# sch.net
KiCad netlist of a schematic drawn in Altium Designer
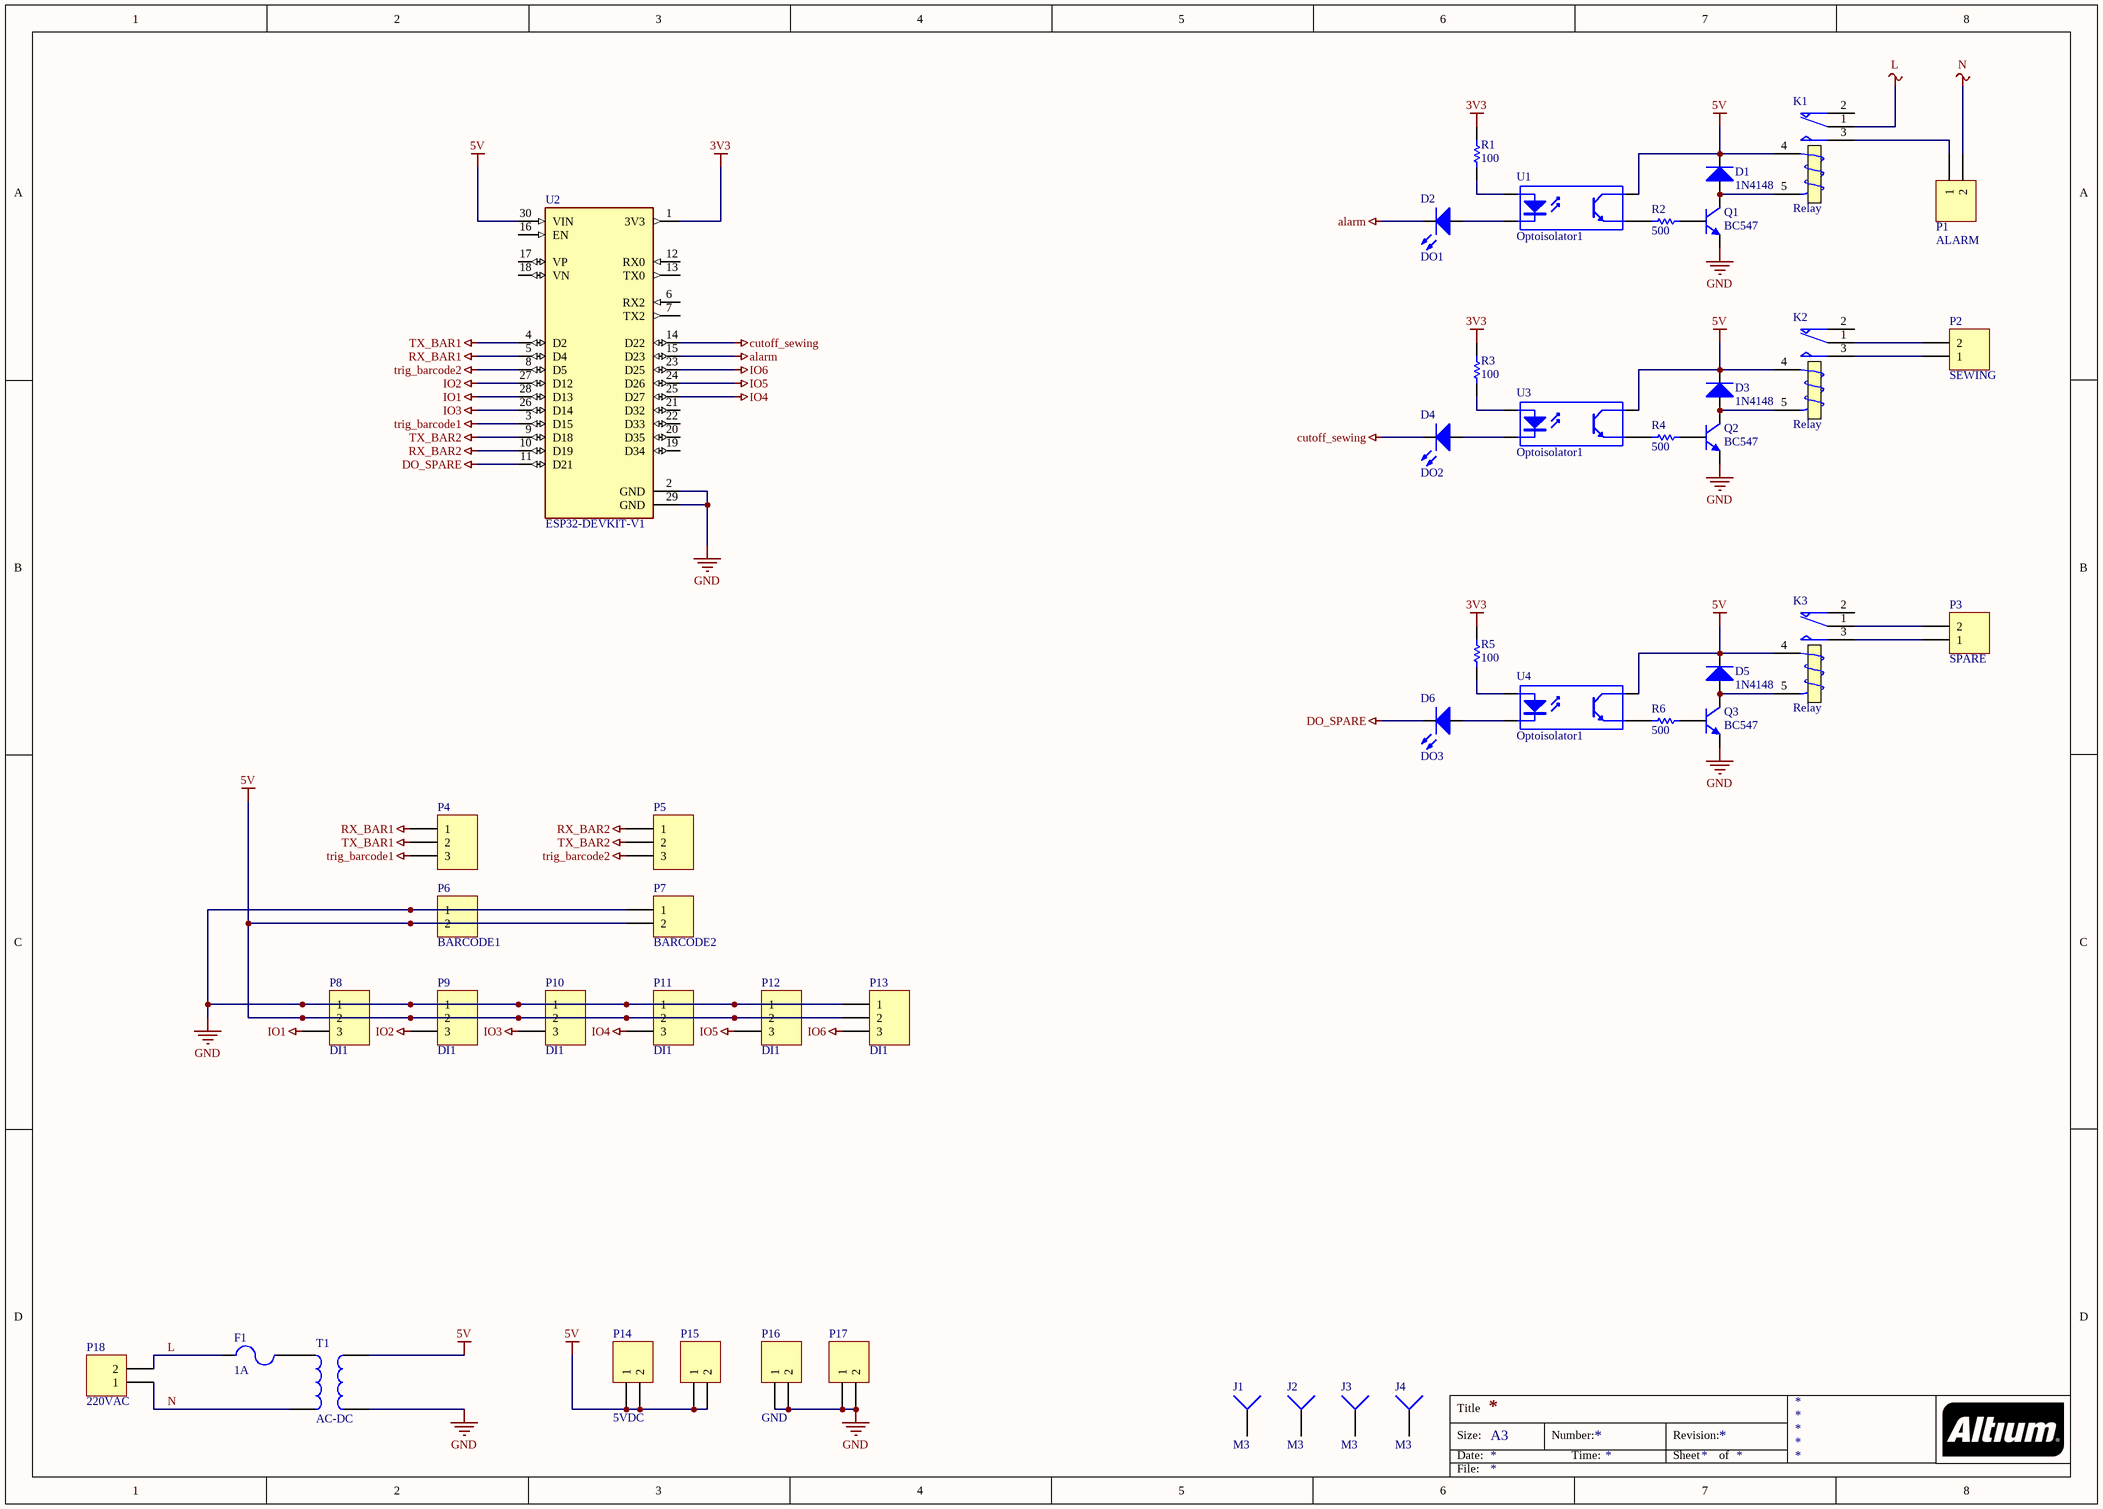
[diagram p0: sch.SchDoc]

(export (version "E")
  (design (tool "Eeschema 10.0.6"))
  (components
    (comp (ref "D1")
      (value "1N4148")
      (footprint "weerachai:D4148")
      (description "Default Diode")
      (fields (field (name "PUBLISHER") "Altium Limited"))
      (libsource (lib "weerachai") (part "Diode"))
    )
    (comp (ref "D2")
      (value "DO1")
      (footprint "weerachai:LED")
      (description "Typical INFRARED GaAs LED")
      (fields (field (name "PUBLISHER") "Altium Limited"))
      (libsource (lib "weerachai") (part "LED0"))
    )
    (comp (ref "D3")
      (value "1N4148")
      (footprint "weerachai:D4148")
      (description "Default Diode")
      (fields (field (name "PUBLISHER") "Altium Limited"))
      (libsource (lib "weerachai") (part "Diode"))
    )
    (comp (ref "D4")
      (value "DO2")
      (footprint "weerachai:LED")
      (description "Typical INFRARED GaAs LED")
      (fields (field (name "PUBLISHER") "Altium Limited"))
      (libsource (lib "weerachai") (part "LED0"))
    )
    (comp (ref "D5")
      (value "1N4148")
      (footprint "weerachai:D4148")
      (description "Default Diode")
      (fields (field (name "PUBLISHER") "Altium Limited"))
      (libsource (lib "weerachai") (part "Diode"))
    )
    (comp (ref "D6")
      (value "DO3")
      (footprint "weerachai:LED")
      (description "Typical INFRARED GaAs LED")
      (fields (field (name "PUBLISHER") "Altium Limited"))
      (libsource (lib "weerachai") (part "LED0"))
    )
    (comp (ref "F1")
      (value "1A")
      (footprint "weerachai:CAP5W")
      (description "Fuse")
      (fields (field (name "PUBLISHER") "Altium Limited"))
      (libsource (lib "weerachai") (part "Fuse 2"))
    )
    (comp (ref "J1")
      (value "M3")
      (footprint "weerachai:PAD")
      (description "Socket")
      (fields (field (name "PUBLISHER") "Altium Limited"))
      (libsource (lib "weerachai") (part "Socket"))
    )
    (comp (ref "J2")
      (value "M3")
      (footprint "weerachai:PAD")
      (description "Socket")
      (fields (field (name "PUBLISHER") "Altium Limited"))
      (libsource (lib "weerachai") (part "Socket"))
    )
    (comp (ref "J3")
      (value "M3")
      (footprint "weerachai:PAD")
      (description "Socket")
      (fields (field (name "PUBLISHER") "Altium Limited"))
      (libsource (lib "weerachai") (part "Socket"))
    )
    (comp (ref "J4")
      (value "M3")
      (footprint "weerachai:PAD")
      (description "Socket")
      (fields (field (name "PUBLISHER") "Altium Limited"))
      (libsource (lib "weerachai") (part "Socket"))
    )
    (comp (ref "K1")
      (value "Relay")
      (footprint "weerachai:RELAY1CON_REV")
      (description "SPDT Relay")
      (fields (field (name "PUBLISHER") "Altium Limited"))
      (libsource (lib "weerachai") (part "Relay"))
    )
    (comp (ref "K2")
      (value "Relay")
      (footprint "weerachai:RELAY1CON_REV")
      (description "SPDT Relay")
      (fields (field (name "PUBLISHER") "Altium Limited"))
      (libsource (lib "weerachai") (part "Relay"))
    )
    (comp (ref "K3")
      (value "Relay")
      (footprint "weerachai:RELAY1CON_REV")
      (description "SPDT Relay")
      (fields (field (name "PUBLISHER") "Altium Limited"))
      (libsource (lib "weerachai") (part "Relay"))
    )
    (comp (ref "P1")
      (value "ALARM")
      (footprint "weerachai:KF142V-5.08-P2")
      (description "Header, 2-Pin")
      (fields (field (name "PUBLISHER") "Altium Limited"))
      (libsource (lib "") (part "Header 2_1"))
    )
    (comp (ref "P2")
      (value "SEWING")
      (footprint "weerachai:KF142V-5.08-P2")
      (description "Header, 2-Pin")
      (fields (field (name "PUBLISHER") "Altium Limited"))
      (libsource (lib "Miscellaneous Connectors") (part "Header 2"))
    )
    (comp (ref "P3")
      (value "SPARE")
      (footprint "weerachai:KF142V-5.08-P2")
      (description "Header, 2-Pin")
      (fields (field (name "PUBLISHER") "Altium Limited"))
      (libsource (lib "Miscellaneous Connectors") (part "Header 2"))
    )
    (comp (ref "P4")
      (value "~")
      (footprint "weerachai:CONNECT_2.54_(3)")
      (description "Header, 3-Pin")
      (fields (field (name "PUBLISHER") "Altium Limited"))
      (libsource (lib "Miscellaneous Connectors") (part "Header 3"))
    )
    (comp (ref "P5")
      (value "~")
      (footprint "weerachai:CONNECT_2.54_(3)")
      (description "Header, 3-Pin")
      (fields (field (name "PUBLISHER") "Altium Limited"))
      (libsource (lib "Miscellaneous Connectors") (part "Header 3"))
    )
    (comp (ref "P6")
      (value "BARCODE1")
      (footprint "weerachai:CONNECT_2.54_(2)")
      (description "Header, 2-Pin")
      (fields (field (name "PUBLISHER") "Altium Limited"))
      (libsource (lib "") (part "Header 2_2"))
    )
    (comp (ref "P7")
      (value "BARCODE2")
      (footprint "weerachai:CONNECT_2.54_(2)")
      (description "Header, 2-Pin")
      (fields (field (name "PUBLISHER") "Altium Limited"))
      (libsource (lib "") (part "Header 2_2"))
    )
    (comp (ref "P8")
      (value "DI1")
      (footprint "weerachai:CONNECT_2.54_(3)")
      (description "Header, 3-Pin")
      (fields (field (name "PUBLISHER") "Altium Limited"))
      (libsource (lib "Miscellaneous Connectors") (part "Header 3"))
    )
    (comp (ref "P9")
      (value "DI1")
      (footprint "weerachai:CONNECT_2.54_(3)")
      (description "Header, 3-Pin")
      (fields (field (name "PUBLISHER") "Altium Limited"))
      (libsource (lib "Miscellaneous Connectors") (part "Header 3"))
    )
    (comp (ref "P10")
      (value "DI1")
      (footprint "weerachai:CONNECT_2.54_(3)")
      (description "Header, 3-Pin")
      (fields (field (name "PUBLISHER") "Altium Limited"))
      (libsource (lib "Miscellaneous Connectors") (part "Header 3"))
    )
    (comp (ref "P11")
      (value "DI1")
      (footprint "weerachai:CONNECT_2.54_(3)")
      (description "Header, 3-Pin")
      (fields (field (name "PUBLISHER") "Altium Limited"))
      (libsource (lib "Miscellaneous Connectors") (part "Header 3"))
    )
    (comp (ref "P12")
      (value "DI1")
      (footprint "weerachai:CONNECT_2.54_(3)")
      (description "Header, 3-Pin")
      (fields (field (name "PUBLISHER") "Altium Limited"))
      (libsource (lib "Miscellaneous Connectors") (part "Header 3"))
    )
    (comp (ref "P13")
      (value "DI1")
      (footprint "weerachai:CONNECT_2.54_(3)")
      (description "Header, 3-Pin")
      (fields (field (name "PUBLISHER") "Altium Limited"))
      (libsource (lib "Miscellaneous Connectors") (part "Header 3"))
    )
    (comp (ref "P14")
      (value "5VDC")
      (footprint "weerachai:KF142V-5.08-P2")
      (description "Header, 2-Pin")
      (fields (field (name "PUBLISHER") "Altium Limited"))
      (libsource (lib "Miscellaneous Connectors") (part "Header 2"))
    )
    (comp (ref "P15")
      (value "~")
      (footprint "weerachai:KF142V-5.08-P2")
      (description "Header, 2-Pin")
      (fields (field (name "PUBLISHER") "Altium Limited"))
      (libsource (lib "Miscellaneous Connectors") (part "Header 2"))
    )
    (comp (ref "P16")
      (value "GND")
      (footprint "weerachai:KF142V-5.08-P2")
      (description "Header, 2-Pin")
      (fields (field (name "PUBLISHER") "Altium Limited"))
      (libsource (lib "Miscellaneous Connectors") (part "Header 2"))
    )
    (comp (ref "P17")
      (value "~")
      (footprint "weerachai:KF142V-5.08-P2")
      (description "Header, 2-Pin")
      (fields (field (name "PUBLISHER") "Altium Limited"))
      (libsource (lib "Miscellaneous Connectors") (part "Header 2"))
    )
    (comp (ref "P18")
      (value "220VAC")
      (footprint "weerachai:KF142V-5.08-P2")
      (description "Header, 2-Pin")
      (fields (field (name "PUBLISHER") "Altium Limited"))
      (libsource (lib "") (part "Header 2_1"))
    )
    (comp (ref "Q1")
      (value "BC547")
      (footprint "weerachai:TO-92")
      (description "NPN General Purpose Amplifier")
      (fields (field (name "PUBLISHER") "Altium Limited"))
      (libsource (lib "weerachai") (part "2N3904"))
    )
    (comp (ref "Q2")
      (value "BC547")
      (footprint "weerachai:TO-92")
      (description "NPN General Purpose Amplifier")
      (fields (field (name "PUBLISHER") "Altium Limited"))
      (libsource (lib "weerachai") (part "2N3904"))
    )
    (comp (ref "Q3")
      (value "BC547")
      (footprint "weerachai:TO-92")
      (description "NPN General Purpose Amplifier")
      (fields (field (name "PUBLISHER") "Altium Limited"))
      (libsource (lib "weerachai") (part "2N3904"))
    )
    (comp (ref "R1")
      (value "100")
      (footprint "weerachai:R1/8")
      (description "Resistor")
      (fields (field (name "PUBLISHER") "Altium Limited"))
      (libsource (lib "weerachai") (part "Res1"))
    )
    (comp (ref "R2")
      (value "500")
      (footprint "weerachai:R1/8")
      (description "Resistor")
      (fields (field (name "PUBLISHER") "Altium Limited"))
      (libsource (lib "weerachai") (part "Res1"))
    )
    (comp (ref "R3")
      (value "100")
      (footprint "weerachai:R1/8")
      (description "Resistor")
      (fields (field (name "PUBLISHER") "Altium Limited"))
      (libsource (lib "weerachai") (part "Res1"))
    )
    (comp (ref "R4")
      (value "500")
      (footprint "weerachai:R1/8")
      (description "Resistor")
      (fields (field (name "PUBLISHER") "Altium Limited"))
      (libsource (lib "weerachai") (part "Res1"))
    )
    (comp (ref "R5")
      (value "100")
      (footprint "weerachai:R1/8")
      (description "Resistor")
      (fields (field (name "PUBLISHER") "Altium Limited"))
      (libsource (lib "weerachai") (part "Res1"))
    )
    (comp (ref "R6")
      (value "500")
      (footprint "weerachai:R1/8")
      (description "Resistor")
      (fields (field (name "PUBLISHER") "Altium Limited"))
      (libsource (lib "weerachai") (part "Res1"))
    )
    (comp (ref "T1")
      (value "AC-DC")
      (footprint "weerachai:AC-DC")
      (description "Transformer")
      (fields (field (name "PUBLISHER") "Altium Limited"))
      (libsource (lib "weerachai") (part "Trans"))
    )
    (comp (ref "U1")
      (value "Optoisolator1")
      (footprint "weerachai:DIP-4 - TOP")
      (description "4-Pin Phototransistor Optocoupler")
      (fields (field (name "PUBLISHER") "Altium Limited"))
      (libsource (lib "weerachai") (part "Optoisolator1"))
    )
    (comp (ref "U2")
      (value "ESP32-DEVKIT-V1")
      (footprint "weerachai:ESP32_DEVKIT_V1")
      (libsource (lib "weerachai") (part "ESP32-DEVKIT-V1"))
    )
    (comp (ref "U3")
      (value "Optoisolator1")
      (footprint "weerachai:DIP-4 - TOP")
      (description "4-Pin Phototransistor Optocoupler")
      (fields (field (name "PUBLISHER") "Altium Limited"))
      (libsource (lib "weerachai") (part "Optoisolator1"))
    )
    (comp (ref "U4")
      (value "Optoisolator1")
      (footprint "weerachai:DIP-4 - TOP")
      (description "4-Pin Phototransistor Optocoupler")
      (fields (field (name "PUBLISHER") "Altium Limited"))
      (libsource (lib "weerachai") (part "Optoisolator1"))
    )
  )
  (nets
    (net (code "1") (name "3V3") (class "Default")
      (node (ref "R1") (pin "2") (pinfunction "2_2") (pintype "passive"))
      (node (ref "R3") (pin "2") (pinfunction "2_2") (pintype "passive"))
      (node (ref "R5") (pin "2") (pinfunction "2_2") (pintype "passive"))
      (node (ref "U2") (pin "1") (pinfunction "3V3_1") (pintype "output"))
    )
    (net (code "2") (name "5V") (class "Default")
      (node (ref "D1") (pin "K") (pinfunction "K_K") (pintype "passive"))
      (node (ref "D3") (pin "K") (pinfunction "K_K") (pintype "passive"))
      (node (ref "D5") (pin "K") (pinfunction "K_K") (pintype "passive"))
      (node (ref "K1") (pin "4") (pinfunction "T1_4") (pintype "passive"))
      (node (ref "K2") (pin "4") (pinfunction "T1_4") (pintype "passive"))
      (node (ref "K3") (pin "4") (pinfunction "T1_4") (pintype "passive"))
      (node (ref "P10") (pin "2") (pinfunction "2_2") (pintype "passive"))
      (node (ref "P11") (pin "2") (pinfunction "2_2") (pintype "passive"))
      (node (ref "P12") (pin "2") (pinfunction "2_2") (pintype "passive"))
      (node (ref "P13") (pin "2") (pinfunction "2_2") (pintype "passive"))
      (node (ref "P14") (pin "1") (pinfunction "1_1") (pintype "passive"))
      (node (ref "P14") (pin "2") (pinfunction "2_2") (pintype "passive"))
      (node (ref "P15") (pin "1") (pinfunction "1_1") (pintype "passive"))
      (node (ref "P15") (pin "2") (pinfunction "2_2") (pintype "passive"))
      (node (ref "P6") (pin "2") (pinfunction "2_2") (pintype "passive"))
      (node (ref "P7") (pin "2") (pinfunction "2_2") (pintype "passive"))
      (node (ref "P8") (pin "2") (pinfunction "2_2") (pintype "passive"))
      (node (ref "P9") (pin "2") (pinfunction "2_2") (pintype "passive"))
      (node (ref "T1") (pin "4") (pinfunction "4_4") (pintype "passive"))
      (node (ref "U1") (pin "4") (pinfunction "C_4") (pintype "passive"))
      (node (ref "U2") (pin "30") (pinfunction "VIN_30") (pintype "input"))
      (node (ref "U3") (pin "4") (pinfunction "C_4") (pintype "passive"))
      (node (ref "U4") (pin "4") (pinfunction "C_4") (pintype "passive"))
    )
    (net (code "3") (name "DO_SPARE") (class "Default")
      (node (ref "D6") (pin "2") (pinfunction "K_2") (pintype "passive"))
      (node (ref "U2") (pin "11") (pinfunction "D21_11") (pintype "bidirectional"))
    )
    (net (code "4") (name "GND") (class "Default")
      (node (ref "P10") (pin "1") (pinfunction "1_1") (pintype "passive"))
      (node (ref "P11") (pin "1") (pinfunction "1_1") (pintype "passive"))
      (node (ref "P12") (pin "1") (pinfunction "1_1") (pintype "passive"))
      (node (ref "P13") (pin "1") (pinfunction "1_1") (pintype "passive"))
      (node (ref "P16") (pin "1") (pinfunction "1_1") (pintype "passive"))
      (node (ref "P16") (pin "2") (pinfunction "2_2") (pintype "passive"))
      (node (ref "P17") (pin "1") (pinfunction "1_1") (pintype "passive"))
      (node (ref "P17") (pin "2") (pinfunction "2_2") (pintype "passive"))
      (node (ref "P6") (pin "1") (pinfunction "1_1") (pintype "passive"))
      (node (ref "P7") (pin "1") (pinfunction "1_1") (pintype "passive"))
      (node (ref "P8") (pin "1") (pinfunction "1_1") (pintype "passive"))
      (node (ref "P9") (pin "1") (pinfunction "1_1") (pintype "passive"))
      (node (ref "Q1") (pin "3") (pinfunction "E_3") (pintype "passive"))
      (node (ref "Q2") (pin "3") (pinfunction "E_3") (pintype "passive"))
      (node (ref "Q3") (pin "3") (pinfunction "E_3") (pintype "passive"))
      (node (ref "T1") (pin "3") (pinfunction "3_3") (pintype "passive"))
      (node (ref "U2") (pin "2") (pinfunction "GND_2") (pintype "power_in"))
      (node (ref "U2") (pin "29") (pinfunction "GND_29") (pintype "power_in"))
    )
    (net (code "5") (name "IO1") (class "Default")
      (node (ref "P8") (pin "3") (pinfunction "3_3") (pintype "passive"))
      (node (ref "U2") (pin "28") (pinfunction "D13_28") (pintype "bidirectional"))
    )
    (net (code "6") (name "IO2") (class "Default")
      (node (ref "P9") (pin "3") (pinfunction "3_3") (pintype "passive"))
      (node (ref "U2") (pin "27") (pinfunction "D12_27") (pintype "bidirectional"))
    )
    (net (code "7") (name "IO3") (class "Default")
      (node (ref "P10") (pin "3") (pinfunction "3_3") (pintype "passive"))
      (node (ref "U2") (pin "26") (pinfunction "D14_26") (pintype "bidirectional"))
    )
    (net (code "8") (name "IO4") (class "Default")
      (node (ref "P11") (pin "3") (pinfunction "3_3") (pintype "passive"))
      (node (ref "U2") (pin "25") (pinfunction "D27_25") (pintype "bidirectional"))
    )
    (net (code "9") (name "IO5") (class "Default")
      (node (ref "P12") (pin "3") (pinfunction "3_3") (pintype "passive"))
      (node (ref "U2") (pin "24") (pinfunction "D26_24") (pintype "bidirectional"))
    )
    (net (code "10") (name "IO6") (class "Default")
      (node (ref "P13") (pin "3") (pinfunction "3_3") (pintype "passive"))
      (node (ref "U2") (pin "23") (pinfunction "D25_23") (pintype "bidirectional"))
    )
    (net (code "11") (name "L") (class "Default")
      (node (ref "F1") (pin "1") (pinfunction "1_1") (pintype "passive"))
      (node (ref "K1") (pin "1") (pinfunction "COM_1") (pintype "passive"))
      (node (ref "P18") (pin "2") (pinfunction "2_2") (pintype "passive"))
    )
    (net (code "12") (name "N") (class "Default")
      (node (ref "P1") (pin "2") (pinfunction "2_2") (pintype "passive"))
      (node (ref "P18") (pin "1") (pinfunction "1_1") (pintype "passive"))
      (node (ref "T1") (pin "1") (pinfunction "1_1") (pintype "passive"))
    )
    (net (code "13") (name "Net-(D2-A)") (class "Default")
      (node (ref "D2") (pin "1") (pinfunction "A_1") (pintype "passive"))
      (node (ref "U1") (pin "2") (pinfunction "K_2") (pintype "passive"))
    )
    (net (code "14") (name "Net-(D4-A)") (class "Default")
      (node (ref "D4") (pin "1") (pinfunction "A_1") (pintype "passive"))
      (node (ref "U3") (pin "2") (pinfunction "K_2") (pintype "passive"))
    )
    (net (code "15") (name "Net-(D6-A)") (class "Default")
      (node (ref "D6") (pin "1") (pinfunction "A_1") (pintype "passive"))
      (node (ref "U4") (pin "2") (pinfunction "K_2") (pintype "passive"))
    )
    (net (code "16") (name "Net-(F1-Pad2)") (class "Default")
      (node (ref "F1") (pin "2") (pinfunction "2_2") (pintype "passive"))
      (node (ref "T1") (pin "2") (pinfunction "2_2") (pintype "passive"))
    )
    (net (code "17") (name "Net-(K1-NO)") (class "Default")
      (node (ref "K1") (pin "3") (pinfunction "NO_3") (pintype "passive"))
      (node (ref "P1") (pin "1") (pinfunction "1_1") (pintype "passive"))
    )
    (net (code "18") (name "Net-(K1-T2)") (class "Default")
      (node (ref "D1") (pin "A") (pinfunction "A_A") (pintype "passive"))
      (node (ref "K1") (pin "5") (pinfunction "T2_5") (pintype "passive"))
      (node (ref "Q1") (pin "1") (pinfunction "C_1") (pintype "passive"))
    )
    (net (code "19") (name "Net-(K2-COM)") (class "Default")
      (node (ref "K2") (pin "1") (pinfunction "COM_1") (pintype "passive"))
      (node (ref "P2") (pin "2") (pinfunction "2_2") (pintype "passive"))
    )
    (net (code "20") (name "Net-(K2-NO)") (class "Default")
      (node (ref "K2") (pin "3") (pinfunction "NO_3") (pintype "passive"))
      (node (ref "P2") (pin "1") (pinfunction "1_1") (pintype "passive"))
    )
    (net (code "21") (name "Net-(K2-T2)") (class "Default")
      (node (ref "D3") (pin "A") (pinfunction "A_A") (pintype "passive"))
      (node (ref "K2") (pin "5") (pinfunction "T2_5") (pintype "passive"))
      (node (ref "Q2") (pin "1") (pinfunction "C_1") (pintype "passive"))
    )
    (net (code "22") (name "Net-(K3-COM)") (class "Default")
      (node (ref "K3") (pin "1") (pinfunction "COM_1") (pintype "passive"))
      (node (ref "P3") (pin "2") (pinfunction "2_2") (pintype "passive"))
    )
    (net (code "23") (name "Net-(K3-NO)") (class "Default")
      (node (ref "K3") (pin "3") (pinfunction "NO_3") (pintype "passive"))
      (node (ref "P3") (pin "1") (pinfunction "1_1") (pintype "passive"))
    )
    (net (code "24") (name "Net-(K3-T2)") (class "Default")
      (node (ref "D5") (pin "A") (pinfunction "A_A") (pintype "passive"))
      (node (ref "K3") (pin "5") (pinfunction "T2_5") (pintype "passive"))
      (node (ref "Q3") (pin "1") (pinfunction "C_1") (pintype "passive"))
    )
    (net (code "25") (name "Net-(Q1-B)") (class "Default")
      (node (ref "Q1") (pin "2") (pinfunction "B_2") (pintype "passive"))
      (node (ref "R2") (pin "1") (pinfunction "1_1") (pintype "passive"))
    )
    (net (code "26") (name "Net-(Q2-B)") (class "Default")
      (node (ref "Q2") (pin "2") (pinfunction "B_2") (pintype "passive"))
      (node (ref "R4") (pin "1") (pinfunction "1_1") (pintype "passive"))
    )
    (net (code "27") (name "Net-(Q3-B)") (class "Default")
      (node (ref "Q3") (pin "2") (pinfunction "B_2") (pintype "passive"))
      (node (ref "R6") (pin "1") (pinfunction "1_1") (pintype "passive"))
    )
    (net (code "28") (name "Net-(U1-A)") (class "Default")
      (node (ref "R1") (pin "1") (pinfunction "1_1") (pintype "passive"))
      (node (ref "U1") (pin "1") (pinfunction "A_1") (pintype "passive"))
    )
    (net (code "29") (name "Net-(U1-E)") (class "Default")
      (node (ref "R2") (pin "2") (pinfunction "2_2") (pintype "passive"))
      (node (ref "U1") (pin "3") (pinfunction "E_3") (pintype "passive"))
    )
    (net (code "30") (name "Net-(U3-A)") (class "Default")
      (node (ref "R3") (pin "1") (pinfunction "1_1") (pintype "passive"))
      (node (ref "U3") (pin "1") (pinfunction "A_1") (pintype "passive"))
    )
    (net (code "31") (name "Net-(U3-E)") (class "Default")
      (node (ref "R4") (pin "2") (pinfunction "2_2") (pintype "passive"))
      (node (ref "U3") (pin "3") (pinfunction "E_3") (pintype "passive"))
    )
    (net (code "32") (name "Net-(U4-A)") (class "Default")
      (node (ref "R5") (pin "1") (pinfunction "1_1") (pintype "passive"))
      (node (ref "U4") (pin "1") (pinfunction "A_1") (pintype "passive"))
    )
    (net (code "33") (name "Net-(U4-E)") (class "Default")
      (node (ref "R6") (pin "2") (pinfunction "2_2") (pintype "passive"))
      (node (ref "U4") (pin "3") (pinfunction "E_3") (pintype "passive"))
    )
    (net (code "34") (name "RX_BAR1") (class "Default")
      (node (ref "P4") (pin "1") (pinfunction "1_1") (pintype "passive"))
      (node (ref "U2") (pin "5") (pinfunction "D4_5") (pintype "bidirectional"))
    )
    (net (code "35") (name "RX_BAR2") (class "Default")
      (node (ref "P5") (pin "1") (pinfunction "1_1") (pintype "passive"))
      (node (ref "U2") (pin "10") (pinfunction "D19_10") (pintype "bidirectional"))
    )
    (net (code "36") (name "TX_BAR1") (class "Default")
      (node (ref "P4") (pin "2") (pinfunction "2_2") (pintype "passive"))
      (node (ref "U2") (pin "4") (pinfunction "D2_4") (pintype "bidirectional"))
    )
    (net (code "37") (name "TX_BAR2") (class "Default")
      (node (ref "P5") (pin "2") (pinfunction "2_2") (pintype "passive"))
      (node (ref "U2") (pin "9") (pinfunction "D18_9") (pintype "bidirectional"))
    )
    (net (code "38") (name "alarm") (class "Default")
      (node (ref "D2") (pin "2") (pinfunction "K_2") (pintype "passive"))
      (node (ref "U2") (pin "15") (pinfunction "D23_15") (pintype "bidirectional"))
    )
    (net (code "39") (name "cutoff_sewing") (class "Default")
      (node (ref "D4") (pin "2") (pinfunction "K_2") (pintype "passive"))
      (node (ref "U2") (pin "14") (pinfunction "D22_14") (pintype "bidirectional"))
    )
    (net (code "40") (name "trig_barcode1") (class "Default")
      (node (ref "P4") (pin "3") (pinfunction "3_3") (pintype "passive"))
      (node (ref "U2") (pin "3") (pinfunction "D15_3") (pintype "bidirectional"))
    )
    (net (code "41") (name "trig_barcode2") (class "Default")
      (node (ref "P5") (pin "3") (pinfunction "3_3") (pintype "passive"))
      (node (ref "U2") (pin "8") (pinfunction "D5_8") (pintype "bidirectional"))
    )
    (net (code "42") (name "unconnected-(J1-Pad1)") (class "Default")
      (node (ref "J1") (pin "1") (pinfunction "1_1") (pintype "passive"))
    )
    (net (code "43") (name "unconnected-(J2-Pad1)") (class "Default")
      (node (ref "J2") (pin "1") (pinfunction "1_1") (pintype "passive"))
    )
    (net (code "44") (name "unconnected-(J3-Pad1)") (class "Default")
      (node (ref "J3") (pin "1") (pinfunction "1_1") (pintype "passive"))
    )
    (net (code "45") (name "unconnected-(J4-Pad1)") (class "Default")
      (node (ref "J4") (pin "1") (pinfunction "1_1") (pintype "passive"))
    )
    (net (code "46") (name "unconnected-(K1-NC-Pad2)") (class "Default")
      (node (ref "K1") (pin "2") (pinfunction "NC_2") (pintype "passive"))
    )
    (net (code "47") (name "unconnected-(K2-NC-Pad2)") (class "Default")
      (node (ref "K2") (pin "2") (pinfunction "NC_2") (pintype "passive"))
    )
    (net (code "48") (name "unconnected-(K3-NC-Pad2)") (class "Default")
      (node (ref "K3") (pin "2") (pinfunction "NC_2") (pintype "passive"))
    )
    (net (code "49") (name "unconnected-(U2-D32-Pad21)") (class "Default")
      (node (ref "U2") (pin "21") (pinfunction "D32_21") (pintype "bidirectional"))
    )
    (net (code "50") (name "unconnected-(U2-D33-Pad22)") (class "Default")
      (node (ref "U2") (pin "22") (pinfunction "D33_22") (pintype "bidirectional"))
    )
    (net (code "51") (name "unconnected-(U2-D34-Pad19)") (class "Default")
      (node (ref "U2") (pin "19") (pinfunction "D34_19") (pintype "bidirectional"))
    )
    (net (code "52") (name "unconnected-(U2-D35-Pad20)") (class "Default")
      (node (ref "U2") (pin "20") (pinfunction "D35_20") (pintype "bidirectional"))
    )
    (net (code "53") (name "unconnected-(U2-EN-Pad16)") (class "Default")
      (node (ref "U2") (pin "16") (pinfunction "EN_16") (pintype "input"))
    )
    (net (code "54") (name "unconnected-(U2-RX0-Pad12)") (class "Default")
      (node (ref "U2") (pin "12") (pinfunction "RX0_12") (pintype "input"))
    )
    (net (code "55") (name "unconnected-(U2-RX2-Pad6)") (class "Default")
      (node (ref "U2") (pin "6") (pinfunction "RX2_6") (pintype "input"))
    )
    (net (code "56") (name "unconnected-(U2-TX0-Pad13)") (class "Default")
      (node (ref "U2") (pin "13") (pinfunction "TX0_13") (pintype "output"))
    )
    (net (code "57") (name "unconnected-(U2-TX2-Pad7)") (class "Default")
      (node (ref "U2") (pin "7") (pinfunction "TX2_7") (pintype "output"))
    )
    (net (code "58") (name "unconnected-(U2-VN-Pad18)") (class "Default")
      (node (ref "U2") (pin "18") (pinfunction "VN_18") (pintype "bidirectional"))
    )
    (net (code "59") (name "unconnected-(U2-VP-Pad17)") (class "Default")
      (node (ref "U2") (pin "17") (pinfunction "VP_17") (pintype "bidirectional"))
    )
  )
)
